# WARP_ESC.net
KiCad netlist of a schematic drawn in Altium Designer
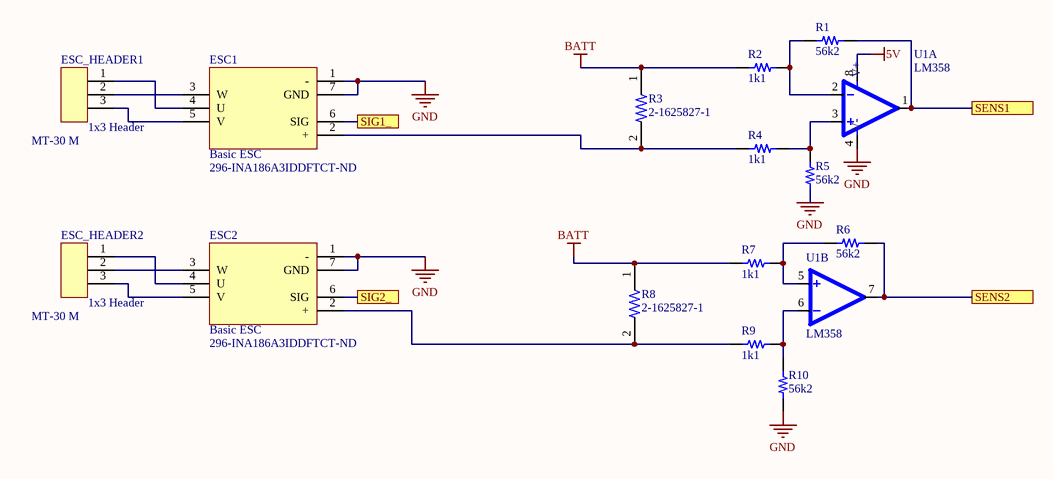
[diagram p0: WARP_ESC.SchDoc]

(export (version "E")
  (design (tool "Eeschema 10.0.6"))
  (components
    (comp (ref "ESC1")
      (value "Basic ESC")
      (footprint "BLUE ESC TOP")
      (fields
        (field (name "MANUFACTURER") "Texas Instruments")
        (field (name "MANUFACTURER PART NUMBER") "INA186A3IDDFT")
        (field (name "SUPPLIER PART NUMBER 1") "296-INA186A3IDDFTCT-ND")
      )
      (libsource (lib "libv1") (part "Basic ESC"))
    )
    (comp (ref "ESC2")
      (value "Basic ESC")
      (footprint "BLUE ESC TOP")
      (fields
        (field (name "MANUFACTURER") "Texas Instruments")
        (field (name "MANUFACTURER PART NUMBER") "INA186A3IDDFT")
        (field (name "SUPPLIER PART NUMBER 1") "296-INA186A3IDDFTCT-ND")
      )
      (libsource (lib "libv1") (part "Basic ESC"))
    )
    (comp (ref "ESC_HEADER1")
      (value "MT-30 M")
      (footprint "MT30-M")
      (libsource (lib "Schlib1") (part "MT-30 M"))
    )
    (comp (ref "ESC_HEADER2")
      (value "MT-30 M")
      (footprint "MT30-M")
      (libsource (lib "Schlib1") (part "MT-30 M"))
    )
    (comp (ref "R1")
      (value "56k2")
      (footprint "RES 1206_3216")
      (description "RES 0.1 OHM 1% 1/2W 1206")
      (fields (field (name "PART NUMBER") "RL1206FR-7W0R1L") (field (name "MANUFACTURER") "Yageo"))
      (libsource (lib "Celestial Altium Library - altium_library") (part "Resistor"))
    )
    (comp (ref "R2")
      (value "1k1")
      (footprint "RES 1206_3216")
      (description "RES 0.1 OHM 1% 1/2W 1206")
      (fields (field (name "PART NUMBER") "RL1206FR-7W0R1L") (field (name "MANUFACTURER") "Yageo"))
      (libsource (lib "Celestial Altium Library - altium_library") (part "Resistor"))
    )
    (comp (ref "R3")
      (value "2-1625827-1")
      (footprint "RESC6331X70N")
      (description "TL3A R002 1% 2K RL")
      (libsource (lib "2512_SMD_SHUNT") (part "2-1625827-1"))
    )
    (comp (ref "R4")
      (value "1k1")
      (footprint "RES 1206_3216")
      (description "RES 0.1 OHM 1% 1/2W 1206")
      (fields (field (name "PART NUMBER") "RL1206FR-7W0R1L") (field (name "MANUFACTURER") "Yageo"))
      (libsource (lib "Celestial Altium Library - altium_library") (part "Resistor"))
    )
    (comp (ref "R5")
      (value "56k2")
      (footprint "RES 1206_3216")
      (description "RES 0.1 OHM 1% 1/2W 1206")
      (fields (field (name "PART NUMBER") "RL1206FR-7W0R1L") (field (name "MANUFACTURER") "Yageo"))
      (libsource (lib "Celestial Altium Library - altium_library") (part "Resistor"))
    )
    (comp (ref "R6")
      (value "56k2")
      (footprint "RES 1206_3216")
      (description "RES 0.1 OHM 1% 1/2W 1206")
      (fields (field (name "PART NUMBER") "RL1206FR-7W0R1L") (field (name "MANUFACTURER") "Yageo"))
      (libsource (lib "Celestial Altium Library - altium_library") (part "Resistor"))
    )
    (comp (ref "R7")
      (value "1k1")
      (footprint "RES 1206_3216")
      (description "RES 0.1 OHM 1% 1/2W 1206")
      (fields (field (name "PART NUMBER") "RL1206FR-7W0R1L") (field (name "MANUFACTURER") "Yageo"))
      (libsource (lib "Celestial Altium Library - altium_library") (part "Resistor"))
    )
    (comp (ref "R8")
      (value "2-1625827-1")
      (footprint "RESC6331X70N")
      (description "TL3A R002 1% 2K RL")
      (libsource (lib "2512_SMD_SHUNT") (part "2-1625827-1"))
    )
    (comp (ref "R9")
      (value "1k1")
      (footprint "RES 1206_3216")
      (description "RES 0.1 OHM 1% 1/2W 1206")
      (fields (field (name "PART NUMBER") "RL1206FR-7W0R1L") (field (name "MANUFACTURER") "Yageo"))
      (libsource (lib "Celestial Altium Library - altium_library") (part "Resistor"))
    )
    (comp (ref "R10")
      (value "56k2")
      (footprint "RES 1206_3216")
      (description "RES 0.1 OHM 1% 1/2W 1206")
      (fields (field (name "PART NUMBER") "RL1206FR-7W0R1L") (field (name "MANUFACTURER") "Yageo"))
      (libsource (lib "Celestial Altium Library - altium_library") (part "Resistor"))
    )
    (comp (ref "U1") (value "LM358") (footprint "LM358") (libsource (lib "libv1") (part "LM358")))
  )
  (nets
    (net (code "1") (name "/SENS1") (class "Default")
      (node (ref "R1") (pin "2") (pinfunction "2_2") (pintype "passive"))
      (node (ref "U1") (pin "1") (pinfunction "OUT_1") (pintype "passive"))
    )
    (net (code "2") (name "/SENS2") (class "Default")
      (node (ref "R6") (pin "2") (pinfunction "2_2") (pintype "passive"))
      (node (ref "U1") (pin "7") (pinfunction "OUT_7") (pintype "passive"))
    )
    (net (code "3") (name "/SIG1_") (class "Default")
      (node (ref "ESC1") (pin "6") (pinfunction "SIG_6") (pintype "passive"))
    )
    (net (code "4") (name "/SIG2_") (class "Default")
      (node (ref "ESC2") (pin "6") (pinfunction "SIG_6") (pintype "passive"))
    )
    (net (code "5") (name "5V") (class "Default")
      (node (ref "U1") (pin "8") (pinfunction "V+_8") (pintype "power_in"))
    )
    (net (code "6") (name "BATT") (class "Default")
      (node (ref "R2") (pin "1") (pinfunction "1_1") (pintype "passive"))
      (node (ref "R3") (pin "1") (pinfunction "1_1") (pintype "passive"))
      (node (ref "R7") (pin "1") (pinfunction "1_1") (pintype "passive"))
      (node (ref "R8") (pin "1") (pinfunction "1_1") (pintype "passive"))
    )
    (net (code "7") (name "GND") (class "Default")
      (node (ref "ESC1") (pin "1") (pinfunction "-_1") (pintype "passive"))
      (node (ref "ESC1") (pin "7") (pinfunction "GND_7") (pintype "passive"))
      (node (ref "ESC2") (pin "1") (pinfunction "-_1") (pintype "passive"))
      (node (ref "ESC2") (pin "7") (pinfunction "GND_7") (pintype "passive"))
      (node (ref "R10") (pin "1") (pinfunction "1_1") (pintype "passive"))
      (node (ref "R5") (pin "1") (pinfunction "1_1") (pintype "passive"))
      (node (ref "U1") (pin "4") (pinfunction "V-_4") (pintype "power_in"))
    )
    (net (code "8") (name "Net-(ESC1-+)") (class "Default")
      (node (ref "ESC1") (pin "2") (pinfunction "+_2") (pintype "passive"))
      (node (ref "R3") (pin "2") (pinfunction "2_2") (pintype "passive"))
      (node (ref "R4") (pin "1") (pinfunction "1_1") (pintype "passive"))
    )
    (net (code "9") (name "Net-(ESC1-U)") (class "Default")
      (node (ref "ESC1") (pin "4") (pinfunction "U_4") (pintype "passive"))
      (node (ref "ESC_HEADER1") (pin "1") (pintype "passive"))
    )
    (net (code "10") (name "Net-(ESC1-V)") (class "Default")
      (node (ref "ESC1") (pin "5") (pinfunction "V_5") (pintype "passive"))
      (node (ref "ESC_HEADER1") (pin "3") (pintype "passive"))
    )
    (net (code "11") (name "Net-(ESC1-W)") (class "Default")
      (node (ref "ESC1") (pin "3") (pinfunction "W_3") (pintype "passive"))
      (node (ref "ESC_HEADER1") (pin "2") (pintype "passive"))
    )
    (net (code "12") (name "Net-(ESC2-+)") (class "Default")
      (node (ref "ESC2") (pin "2") (pinfunction "+_2") (pintype "passive"))
      (node (ref "R8") (pin "2") (pinfunction "2_2") (pintype "passive"))
      (node (ref "R9") (pin "1") (pinfunction "1_1") (pintype "passive"))
    )
    (net (code "13") (name "Net-(ESC2-U)") (class "Default")
      (node (ref "ESC2") (pin "4") (pinfunction "U_4") (pintype "passive"))
      (node (ref "ESC_HEADER2") (pin "1") (pintype "passive"))
    )
    (net (code "14") (name "Net-(ESC2-V)") (class "Default")
      (node (ref "ESC2") (pin "5") (pinfunction "V_5") (pintype "passive"))
      (node (ref "ESC_HEADER2") (pin "3") (pintype "passive"))
    )
    (net (code "15") (name "Net-(ESC2-W)") (class "Default")
      (node (ref "ESC2") (pin "3") (pinfunction "W_3") (pintype "passive"))
      (node (ref "ESC_HEADER2") (pin "2") (pintype "passive"))
    )
    (net (code "16") (name "Net-(U1A-+IN)") (class "Default")
      (node (ref "R4") (pin "2") (pinfunction "2_2") (pintype "passive"))
      (node (ref "R5") (pin "2") (pinfunction "2_2") (pintype "passive"))
      (node (ref "U1") (pin "3") (pinfunction "+IN_3") (pintype "passive"))
    )
    (net (code "17") (name "Net-(U1A--IN)") (class "Default")
      (node (ref "R1") (pin "1") (pinfunction "1_1") (pintype "passive"))
      (node (ref "R2") (pin "2") (pinfunction "2_2") (pintype "passive"))
      (node (ref "U1") (pin "2") (pinfunction "-IN_2") (pintype "passive"))
    )
    (net (code "18") (name "Net-(U1B-+IN)") (class "Default")
      (node (ref "R6") (pin "1") (pinfunction "1_1") (pintype "passive"))
      (node (ref "R7") (pin "2") (pinfunction "2_2") (pintype "passive"))
      (node (ref "U1") (pin "5") (pinfunction "+IN_5") (pintype "passive"))
    )
    (net (code "19") (name "Net-(U1B--IN)") (class "Default")
      (node (ref "R10") (pin "2") (pinfunction "2_2") (pintype "passive"))
      (node (ref "R9") (pin "2") (pinfunction "2_2") (pintype "passive"))
      (node (ref "U1") (pin "6") (pinfunction "-IN_6") (pintype "passive"))
    )
  )
)
